# 2_STM32F334R8T6Board_Interfaces.net
KiCad netlist of a schematic drawn in Altium Designer
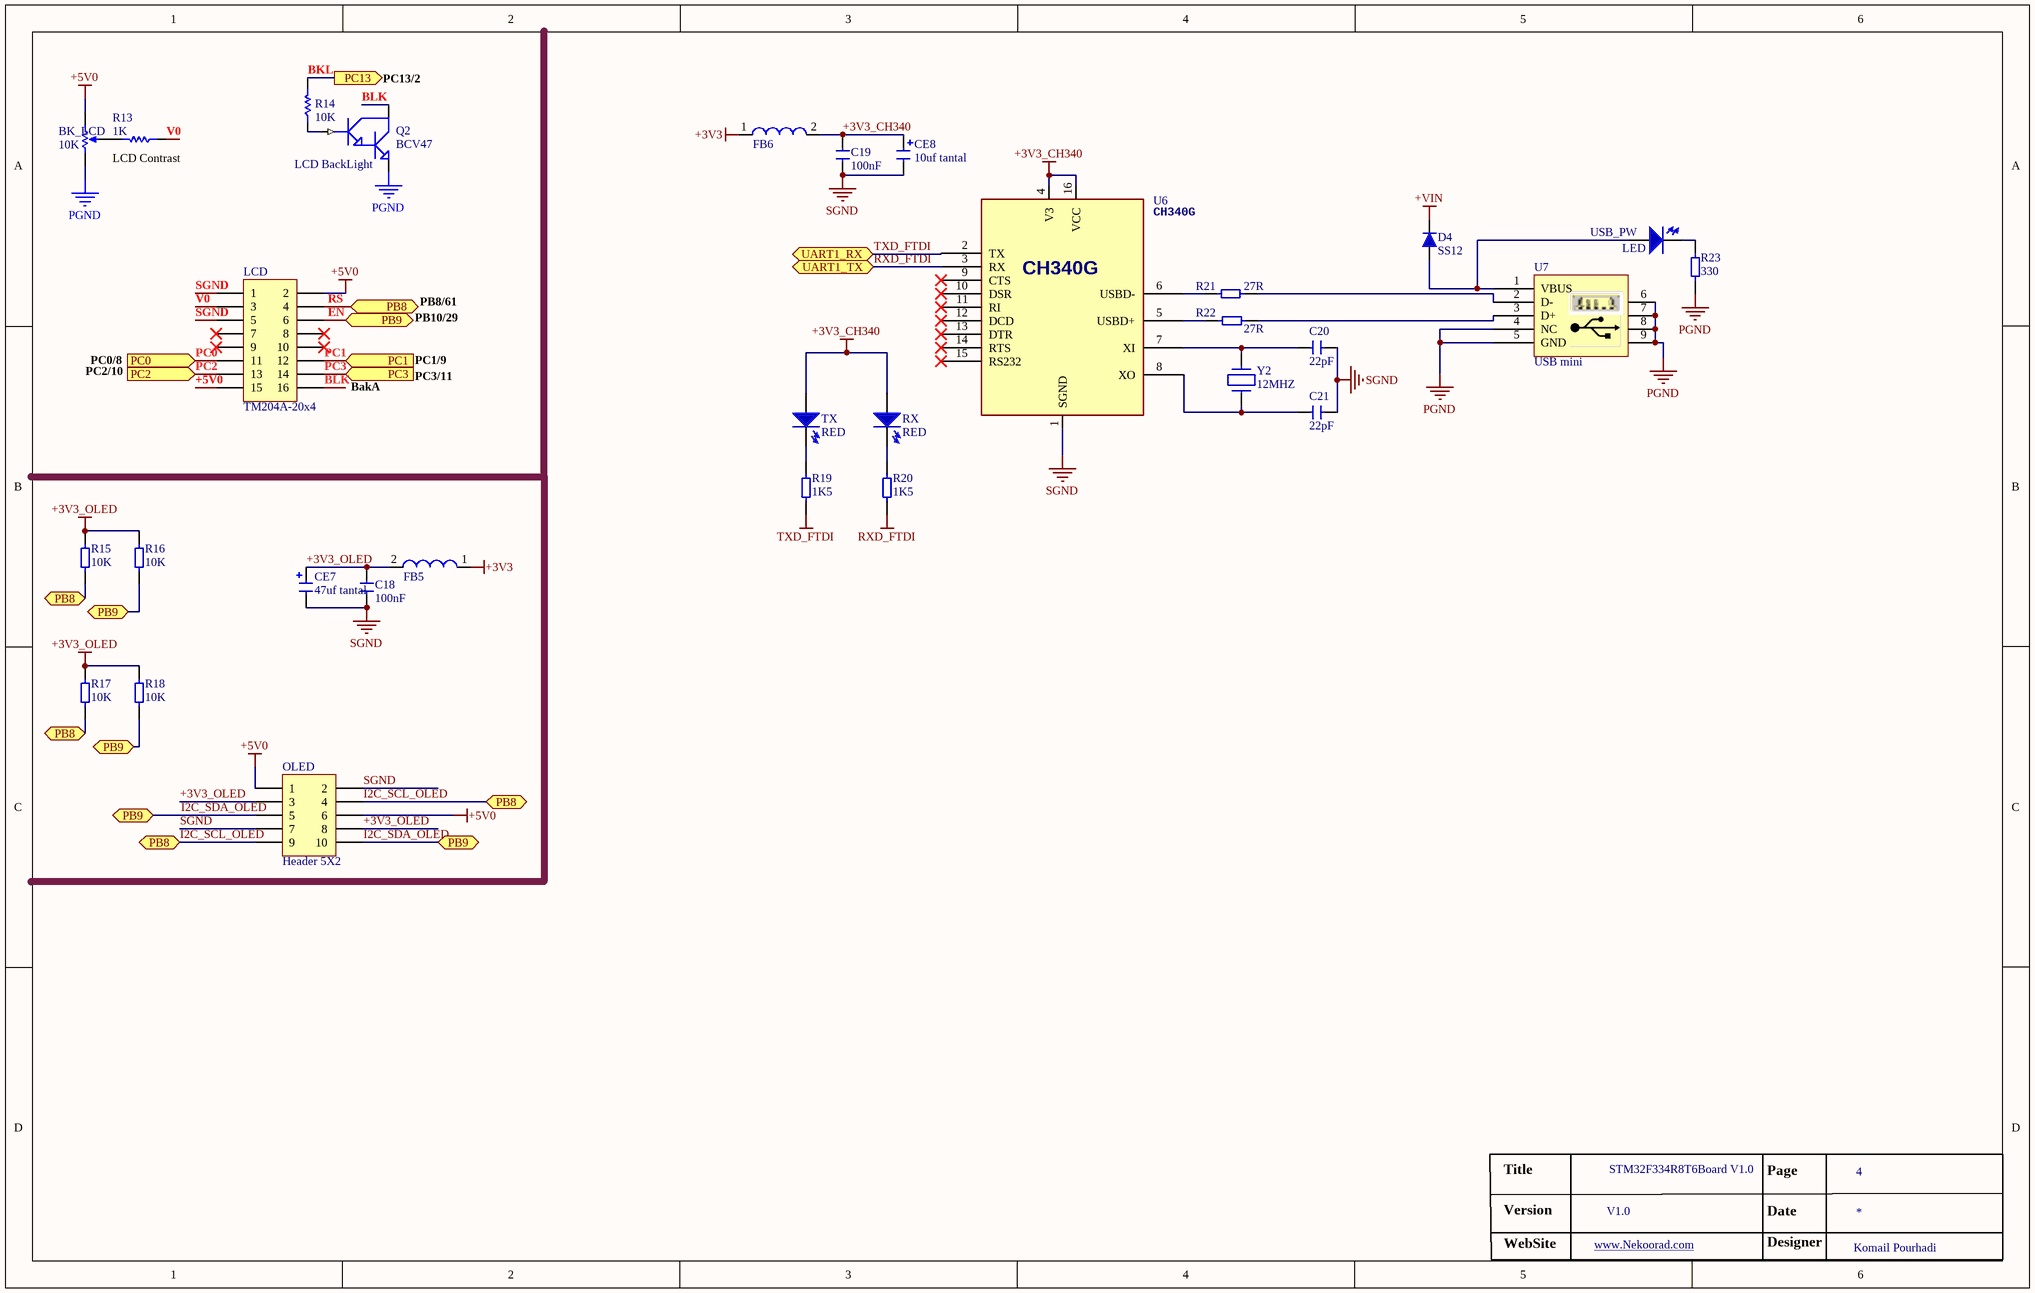
[diagram p0: [2]STM32F334R8T6Board_Interfaces.SchDoc]

(export (version "E")
  (design (tool "Eeschema 10.0.6"))
  (components
    (comp (ref "BK_LCD")
      (value "10K")
      (footprint "JFP")
      (description "Potentiometer")
      (fields (field (name "Comment") "RPot") (field (name "PUBLISHER") "Altium Limited"))
      (libsource (lib "Miscellaneous Devices") (part "RPot"))
    )
    (comp (ref "C18")
      (value "Comment")
      (footprint "SMD_CAP_1206")
      (fields (field (name "ALTIUM_UNNAMED_1") "100nF"))
      (libsource (lib "DotexGroup_LIB") (part "Capacitor SMD"))
    )
    (comp (ref "C19")
      (value "Comment")
      (footprint "SMD_CAP_1206")
      (fields (field (name "ALTIUM_UNNAMED_1") "100nF"))
      (libsource (lib "DotexGroup_LIB") (part "Capacitor SMD"))
    )
    (comp (ref "C20")
      (value "Comment")
      (footprint "SMD_CAP_1206")
      (fields (field (name "ALTIUM_UNNAMED_1") "22pF"))
      (libsource (lib "DotexGroup_LIB") (part "Capacitor SMD"))
    )
    (comp (ref "C21")
      (value "Comment")
      (footprint "SMD_CAP_1206")
      (fields (field (name "ALTIUM_UNNAMED_1") "22pF"))
      (libsource (lib "DotexGroup_LIB") (part "Capacitor SMD"))
    )
    (comp (ref "CE7")
      (value "47uf tantal")
      (footprint "CAP-E-3")
      (libsource (lib "DotexGroup_LIB") (part "Capacitor Tantalium"))
    )
    (comp (ref "CE8")
      (value "10uf tantal")
      (footprint "cap-e-2")
      (libsource (lib "DotexGroup_LIB") (part "Capacitor Tantalium"))
    )
    (comp (ref "D4")
      (value "SS12")
      (footprint "Diode SMA-M")
      (libsource (lib "DotexGroup_LIB") (part "1N4001"))
    )
    (comp (ref "FB5") (value "Comment") (footprint "r4p") (libsource (lib "") (part "Ferrit Bead_1")))
    (comp (ref "FB6")
      (value "Comment")
      (footprint "r4p")
      (libsource (lib "DotexGroup_LIB") (part "Ferrit Bead"))
    )
    (comp (ref "LCD")
      (value "TM204A-20x4")
      (footprint "IDC16_BOX")
      (description "Header, 8-Pin, Dual row")
      (fields (field (name "PUBLISHER") "Altium Limited"))
      (libsource (lib "Miscellaneous Connectors") (part "Header 8X2"))
    )
    (comp (ref "OLED")
      (value "Header 5X2")
      (footprint "IDC10-BOX")
      (description "Header, 5-Pin, Dual row")
      (fields (field (name "PUBLISHER") "Altium Limited"))
      (libsource (lib "Miscellaneous Connectors") (part "Header 5X2"))
    )
    (comp (ref "Q2")
      (value "BCV47")
      (footprint "SOT23_BEC_M")
      (libsource (lib "MyAltiumLib") (part "NPN DAR"))
    )
    (comp (ref "R13")
      (value "1K")
      (footprint "RES_1206")
      (description "Resistor")
      (fields (field (name "TOLERANCE") "5%") (field (name "POWER") "1/8 W"))
      (libsource (lib "My Library") (part "Resistor"))
    )
    (comp (ref "R14")
      (value "10K")
      (footprint "RES_1206")
      (description "Resistor")
      (fields (field (name "TOLERANCE") "5%") (field (name "POWER") "1/8 W"))
      (libsource (lib "My Library") (part "Resistor"))
    )
    (comp (ref "R15")
      (value "RESISTOR")
      (footprint "RES_1206")
      (fields (field (name "ALTIUM_UNNAMED_1") "10K"))
      (libsource (lib "ZetaBoard_Lib") (part "Resistor SMD"))
    )
    (comp (ref "R16")
      (value "RESISTOR")
      (footprint "RES_1206")
      (fields (field (name "ALTIUM_UNNAMED_1") "10K"))
      (libsource (lib "ZetaBoard_Lib") (part "Resistor SMD"))
    )
    (comp (ref "R17")
      (value "RESISTOR")
      (footprint "RES_1206")
      (fields (field (name "ALTIUM_UNNAMED_1") "10K"))
      (libsource (lib "ZetaBoard_Lib") (part "Resistor SMD"))
    )
    (comp (ref "R18")
      (value "RESISTOR")
      (footprint "RES_1206")
      (fields (field (name "ALTIUM_UNNAMED_1") "10K"))
      (libsource (lib "ZetaBoard_Lib") (part "Resistor SMD"))
    )
    (comp (ref "R19")
      (value "RESISTOR")
      (footprint "RES_1206")
      (fields (field (name "ALTIUM_UNNAMED_1") "1K5"))
      (libsource (lib "ZetaBoard_Lib") (part "Resistor SMD"))
    )
    (comp (ref "R20")
      (value "RESISTOR")
      (footprint "RES_1206")
      (fields (field (name "ALTIUM_UNNAMED_1") "1K5"))
      (libsource (lib "ZetaBoard_Lib") (part "Resistor SMD"))
    )
    (comp (ref "R21")
      (value "Comment")
      (footprint "RES_1206")
      (fields (field (name "ALTIUM_UNNAMED_1") "27R"))
      (libsource (lib "DotexGroup_LIB") (part "Resistor SMD"))
    )
    (comp (ref "R22")
      (value "Comment")
      (footprint "RES_1206")
      (fields (field (name "ALTIUM_UNNAMED_1") "27R"))
      (libsource (lib "DotexGroup_LIB") (part "Resistor SMD"))
    )
    (comp (ref "R23")
      (value "Comment")
      (footprint "RES_1206")
      (fields (field (name "ALTIUM_UNNAMED_1") "330"))
      (libsource (lib "DotexGroup_LIB") (part "Resistor SMD"))
    )
    (comp (ref "RX")
      (value "RED")
      (footprint "LED SMD 1206")
      (libsource (lib "DotexGroup_LIB") (part "LED SMD"))
    )
    (comp (ref "TX")
      (value "RED")
      (footprint "LED SMD 1206")
      (libsource (lib "DotexGroup_LIB") (part "LED SMD"))
    )
    (comp (ref "U6")
      (value "CH340G")
      (footprint "Header smd 2*8")
      (description "USB-UART")
      (libsource (lib "DotexGroup_LIB") (part "CH340G_SOP16"))
    )
    (comp (ref "U7")
      (value "USB mini")
      (footprint "SMD_Mini USB Connector")
      (description "mini USB Connector")
      (libsource (lib "My Library") (part "USB mini"))
    )
    (comp (ref "USB_PW")
      (value "LED")
      (footprint "LED SMD 1206")
      (libsource (lib "DotexGroup_LIB") (part "LED SMD"))
    )
    (comp (ref "Y2")
      (value "12MHZ")
      (footprint "Crystal SMD")
      (libsource (lib "DotexGroup_LIB") (part "Xtal"))
    )
  )
  (nets
    (net (code "1") (name "+3V3") (class "Default")
      (node (ref "FB5") (pin "1") (pinfunction "1_1") (pintype "passive"))
      (node (ref "FB6") (pin "1") (pinfunction "1_1") (pintype "passive"))
    )
    (net (code "2") (name "+3V3_CH340") (class "Default")
      (node (ref "C19") (pin "2") (pintype "passive"))
      (node (ref "CE8") (pin "1") (pintype "passive"))
      (node (ref "FB6") (pin "2") (pinfunction "2_2") (pintype "passive"))
      (node (ref "RX") (pin "1") (pinfunction "A_1") (pintype "passive"))
      (node (ref "TX") (pin "1") (pinfunction "A_1") (pintype "passive"))
      (node (ref "U6") (pin "16") (pinfunction "VCC_16") (pintype "passive"))
      (node (ref "U6") (pin "4") (pinfunction "V3_4") (pintype "passive"))
    )
    (net (code "3") (name "+3V3_OLED") (class "Default")
      (node (ref "C18") (pin "2") (pintype "passive"))
      (node (ref "CE7") (pin "1") (pintype "passive"))
      (node (ref "FB5") (pin "2") (pinfunction "2_2") (pintype "passive"))
      (node (ref "OLED") (pin "3") (pinfunction "3_3") (pintype "passive"))
      (node (ref "OLED") (pin "8") (pinfunction "8_8") (pintype "passive"))
      (node (ref "R15") (pin "1") (pintype "passive"))
      (node (ref "R16") (pin "1") (pintype "passive"))
      (node (ref "R17") (pin "1") (pintype "passive"))
      (node (ref "R18") (pin "1") (pintype "passive"))
    )
    (net (code "4") (name "+5V0") (class "Default")
      (node (ref "BK_LCD") (pin "3") (pinfunction "BOT_3") (pintype "passive"))
      (node (ref "LCD") (pin "15") (pinfunction "15_15") (pintype "passive"))
      (node (ref "LCD") (pin "2") (pinfunction "2_2") (pintype "passive"))
      (node (ref "OLED") (pin "1") (pinfunction "1_1") (pintype "passive"))
      (node (ref "OLED") (pin "6") (pinfunction "6_6") (pintype "passive"))
    )
    (net (code "5") (name "+VIN") (class "Default")
      (node (ref "D4") (pin "2") (pinfunction "K_2") (pintype "passive"))
    )
    (net (code "6") (name "/BKL") (class "Default")
      (node (ref "R14") (pin "2") (pinfunction "2_2") (pintype "passive"))
    )
    (net (code "7") (name "/BLK") (class "Default")
      (node (ref "LCD") (pin "16") (pinfunction "16_16") (pintype "passive"))
      (node (ref "Q2") (pin "3") (pinfunction "C_3") (pintype "passive"))
    )
    (net (code "8") (name "/EN") (class "Default")
      (node (ref "LCD") (pin "6") (pinfunction "6_6") (pintype "passive"))
      (node (ref "OLED") (pin "10") (pinfunction "10_10") (pintype "passive"))
      (node (ref "OLED") (pin "5") (pinfunction "5_5") (pintype "passive"))
      (node (ref "R16") (pin "2") (pintype "passive"))
      (node (ref "R18") (pin "2") (pintype "passive"))
    )
    (net (code "9") (name "/I2C_SCL_OLED") (class "Default")
      (node (ref "LCD") (pin "4") (pinfunction "4_4") (pintype "passive"))
      (node (ref "OLED") (pin "4") (pinfunction "4_4") (pintype "passive"))
      (node (ref "OLED") (pin "9") (pinfunction "9_9") (pintype "passive"))
      (node (ref "R15") (pin "2") (pintype "passive"))
      (node (ref "R17") (pin "2") (pintype "passive"))
    )
    (net (code "10") (name "/PC0") (class "Default")
      (node (ref "LCD") (pin "11") (pinfunction "11_11") (pintype "passive"))
    )
    (net (code "11") (name "/PC1") (class "Default")
      (node (ref "LCD") (pin "12") (pinfunction "12_12") (pintype "passive"))
    )
    (net (code "12") (name "/PC2") (class "Default")
      (node (ref "LCD") (pin "13") (pinfunction "13_13") (pintype "passive"))
    )
    (net (code "13") (name "/PC3") (class "Default")
      (node (ref "LCD") (pin "14") (pinfunction "14_14") (pintype "passive"))
    )
    (net (code "14") (name "/V0") (class "Default")
      (node (ref "LCD") (pin "3") (pinfunction "3_3") (pintype "passive"))
      (node (ref "R13") (pin "1") (pinfunction "1_1") (pintype "passive"))
    )
    (net (code "15") (name "Net-(BK_LCD-TAP)") (class "Default")
      (node (ref "BK_LCD") (pin "2") (pinfunction "TAP_2") (pintype "passive"))
      (node (ref "R13") (pin "2") (pinfunction "2_2") (pintype "passive"))
    )
    (net (code "16") (name "Net-(D4-A)") (class "Default")
      (node (ref "D4") (pin "1") (pinfunction "A_1") (pintype "passive"))
      (node (ref "U7") (pin "1") (pinfunction "VBUS_1") (pintype "power_in"))
      (node (ref "USB_PW") (pin "1") (pinfunction "A_1") (pintype "passive"))
    )
    (net (code "17") (name "Net-(Q2-B)") (class "Default")
      (node (ref "Q2") (pin "1") (pinfunction "B_1") (pintype "input"))
      (node (ref "R14") (pin "1") (pinfunction "1_1") (pintype "passive"))
    )
    (net (code "18") (name "Net-(RX-K)") (class "Default")
      (node (ref "R20") (pin "2") (pintype "passive"))
      (node (ref "RX") (pin "2") (pinfunction "K_2") (pintype "passive"))
    )
    (net (code "19") (name "Net-(TX-K)") (class "Default")
      (node (ref "R19") (pin "2") (pintype "passive"))
      (node (ref "TX") (pin "2") (pinfunction "K_2") (pintype "passive"))
    )
    (net (code "20") (name "Net-(U6-USBD+)") (class "Default")
      (node (ref "R22") (pin "1") (pintype "passive"))
      (node (ref "U6") (pin "5") (pinfunction "USBD+_5") (pintype "passive"))
    )
    (net (code "21") (name "Net-(U6-USBD-)") (class "Default")
      (node (ref "R21") (pin "1") (pintype "passive"))
      (node (ref "U6") (pin "6") (pinfunction "USBD-_6") (pintype "passive"))
    )
    (net (code "22") (name "Net-(U6-XI)") (class "Default")
      (node (ref "C20") (pin "2") (pintype "passive"))
      (node (ref "U6") (pin "7") (pinfunction "XI_7") (pintype "passive"))
      (node (ref "Y2") (pin "2") (pintype "passive"))
    )
    (net (code "23") (name "Net-(U6-XO)") (class "Default")
      (node (ref "C21") (pin "1") (pintype "passive"))
      (node (ref "U6") (pin "8") (pinfunction "XO_8") (pintype "passive"))
      (node (ref "Y2") (pin "1") (pintype "passive"))
    )
    (net (code "24") (name "Net-(U7-D+)") (class "Default")
      (node (ref "R22") (pin "2") (pintype "passive"))
      (node (ref "U7") (pin "3") (pinfunction "D+_3") (pintype "passive"))
    )
    (net (code "25") (name "Net-(U7-D-)") (class "Default")
      (node (ref "R21") (pin "2") (pintype "passive"))
      (node (ref "U7") (pin "2") (pinfunction "D-_2") (pintype "passive"))
    )
    (net (code "26") (name "Net-(USB_PW-K)") (class "Default")
      (node (ref "R23") (pin "1") (pintype "passive"))
      (node (ref "USB_PW") (pin "2") (pinfunction "K_2") (pintype "passive"))
    )
    (net (code "27") (name "PGND") (class "Default")
      (node (ref "BK_LCD") (pin "1") (pinfunction "TOP_1") (pintype "passive"))
      (node (ref "Q2") (pin "2") (pinfunction "E_2") (pintype "passive"))
      (node (ref "R23") (pin "2") (pintype "passive"))
      (node (ref "U7") (pin "4") (pinfunction "NC_4") (pintype "power_in"))
      (node (ref "U7") (pin "5") (pinfunction "GND_5") (pintype "power_in"))
      (node (ref "U7") (pin "6") (pinfunction "6_6") (pintype "passive"))
      (node (ref "U7") (pin "7") (pinfunction "7_7") (pintype "passive"))
      (node (ref "U7") (pin "8") (pinfunction "8_8") (pintype "passive"))
      (node (ref "U7") (pin "9") (pinfunction "9_9") (pintype "passive"))
    )
    (net (code "28") (name "RXD_FTDI") (class "Default")
      (node (ref "R20") (pin "1") (pintype "passive"))
      (node (ref "U6") (pin "3") (pinfunction "RX_3") (pintype "passive"))
    )
    (net (code "29") (name "SGND") (class "Default")
      (node (ref "C18") (pin "1") (pintype "passive"))
      (node (ref "C19") (pin "1") (pintype "passive"))
      (node (ref "C20") (pin "1") (pintype "passive"))
      (node (ref "C21") (pin "2") (pintype "passive"))
      (node (ref "CE7") (pin "2") (pintype "passive"))
      (node (ref "CE8") (pin "2") (pintype "passive"))
      (node (ref "LCD") (pin "1") (pinfunction "1_1") (pintype "passive"))
      (node (ref "LCD") (pin "5") (pinfunction "5_5") (pintype "passive"))
      (node (ref "OLED") (pin "2") (pinfunction "2_2") (pintype "passive"))
      (node (ref "OLED") (pin "7") (pinfunction "7_7") (pintype "passive"))
      (node (ref "U6") (pin "1") (pinfunction "SGND_1") (pintype "passive"))
    )
    (net (code "30") (name "TXD_FTDI") (class "Default")
      (node (ref "R19") (pin "1") (pintype "passive"))
      (node (ref "U6") (pin "2") (pinfunction "TX_2") (pintype "passive"))
    )
    (net (code "31") (name "unconnected-(LCD-Pad7)") (class "Default")
      (node (ref "LCD") (pin "7") (pinfunction "7_7") (pintype "passive+no_connect"))
    )
    (net (code "32") (name "unconnected-(LCD-Pad8)") (class "Default")
      (node (ref "LCD") (pin "8") (pinfunction "8_8") (pintype "passive+no_connect"))
    )
    (net (code "33") (name "unconnected-(LCD-Pad9)") (class "Default")
      (node (ref "LCD") (pin "9") (pinfunction "9_9") (pintype "passive+no_connect"))
    )
    (net (code "34") (name "unconnected-(LCD-Pad10)") (class "Default")
      (node (ref "LCD") (pin "10") (pinfunction "10_10") (pintype "passive+no_connect"))
    )
    (net (code "35") (name "unconnected-(U6-CTS-Pad9)") (class "Default")
      (node (ref "U6") (pin "9") (pinfunction "CTS_9") (pintype "passive+no_connect"))
    )
    (net (code "36") (name "unconnected-(U6-DCD-Pad12)") (class "Default")
      (node (ref "U6") (pin "12") (pinfunction "DCD_12") (pintype "passive+no_connect"))
    )
    (net (code "37") (name "unconnected-(U6-DSR-Pad10)") (class "Default")
      (node (ref "U6") (pin "10") (pinfunction "DSR_10") (pintype "passive+no_connect"))
    )
    (net (code "38") (name "unconnected-(U6-DTR-Pad13)") (class "Default")
      (node (ref "U6") (pin "13") (pinfunction "DTR_13") (pintype "passive+no_connect"))
    )
    (net (code "39") (name "unconnected-(U6-RI-Pad11)") (class "Default")
      (node (ref "U6") (pin "11") (pinfunction "RI_11") (pintype "passive+no_connect"))
    )
    (net (code "40") (name "unconnected-(U6-RS232-Pad15)") (class "Default")
      (node (ref "U6") (pin "15") (pinfunction "RS232_15") (pintype "passive+no_connect"))
    )
    (net (code "41") (name "unconnected-(U6-RTS-Pad14)") (class "Default")
      (node (ref "U6") (pin "14") (pinfunction "RTS_14") (pintype "passive+no_connect"))
    )
  )
)
